# 02-Memory.net
KiCad netlist of a schematic drawn in Altium Designer
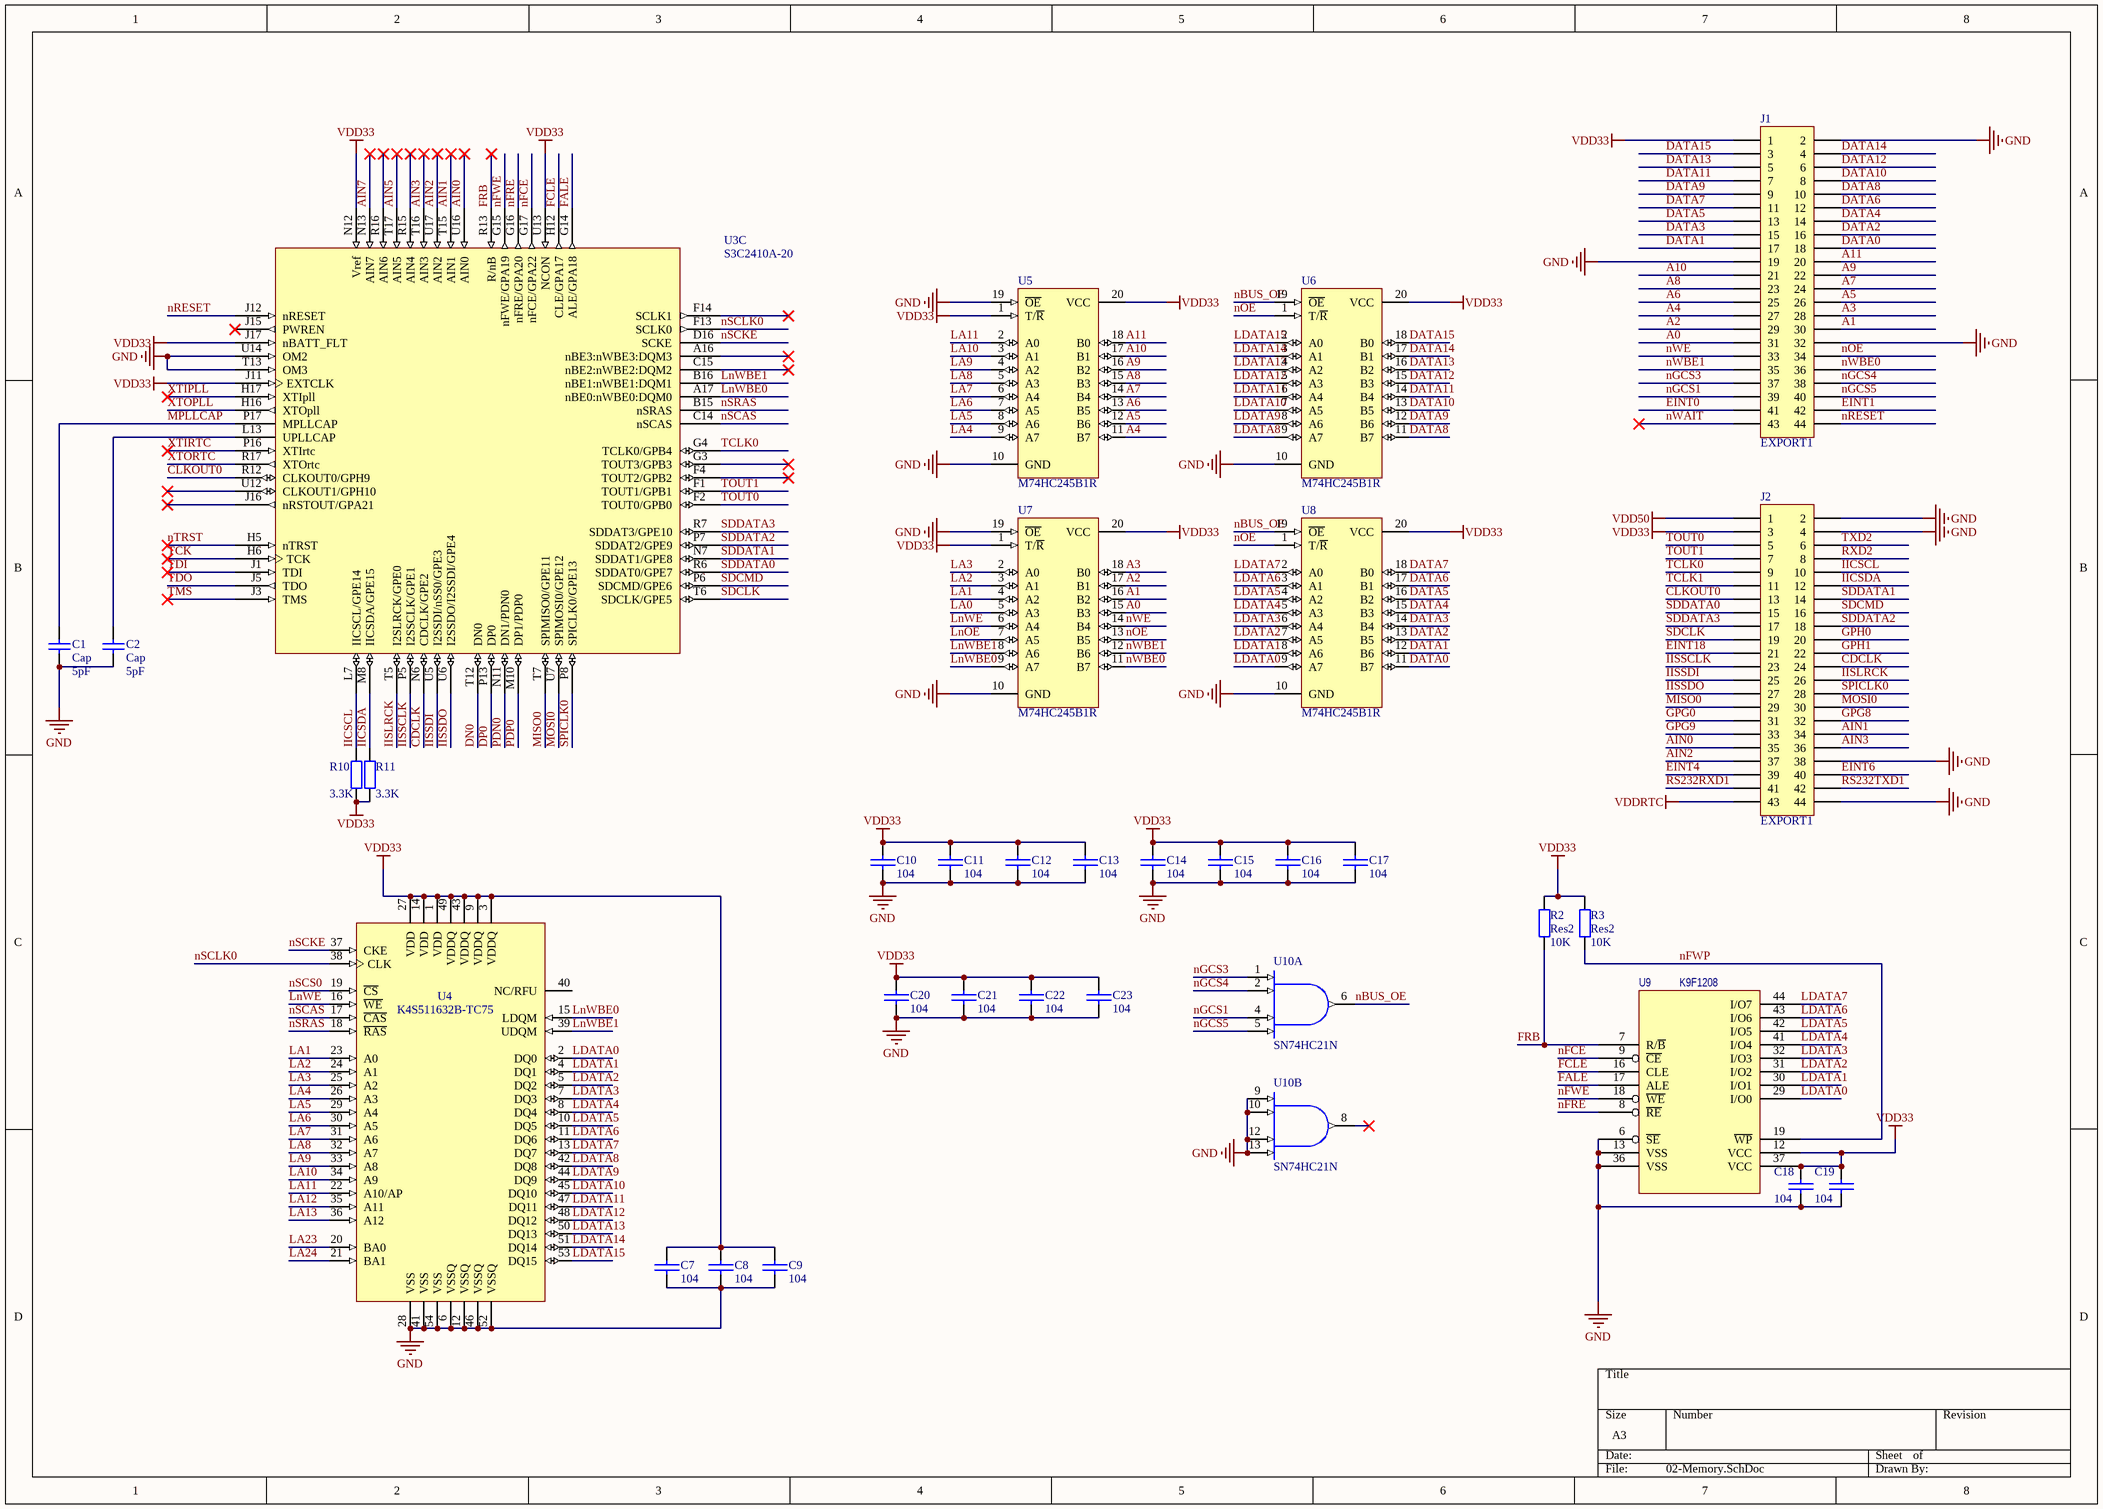
[diagram p0: 02-Memory.SchDoc]

(export (version "E")
  (design (tool "Eeschema 10.0.6"))
  (components
    (comp (ref "C1")
      (value "Cap")
      (footprint "RAD-0.3")
      (description "Capacitor")
      (fields (field (name "ALTIUM_VALUE") "5pF") (field (name "PUBLISHER") "Altium Limited"))
      (libsource (lib "Miscellaneous Devices") (part "Cap"))
    )
    (comp (ref "C2")
      (value "Cap")
      (footprint "RAD-0.3")
      (description "Capacitor")
      (fields (field (name "ALTIUM_VALUE") "5pF") (field (name "PUBLISHER") "Altium Limited"))
      (libsource (lib "Miscellaneous Devices") (part "Cap"))
    )
    (comp (ref "C7")
      (value "104")
      (footprint "A型钽电容")
      (description "Capacitor")
      (libsource (lib "ARM_DEMO") (part "CAP_1"))
    )
    (comp (ref "C8")
      (value "104")
      (footprint "A型钽电容")
      (description "Capacitor")
      (libsource (lib "ARM_DEMO") (part "CAP_1"))
    )
    (comp (ref "C9")
      (value "104")
      (footprint "A型钽电容")
      (description "Capacitor")
      (libsource (lib "ARM_DEMO") (part "CAP_1"))
    )
    (comp (ref "C10")
      (value "104")
      (footprint "A型钽电容")
      (description "Capacitor")
      (libsource (lib "ARM_DEMO") (part "CAP_1"))
    )
    (comp (ref "C11")
      (value "104")
      (footprint "A型钽电容")
      (description "Capacitor")
      (libsource (lib "ARM_DEMO") (part "CAP_1"))
    )
    (comp (ref "C12")
      (value "104")
      (footprint "A型钽电容")
      (description "Capacitor")
      (libsource (lib "ARM_DEMO") (part "CAP_1"))
    )
    (comp (ref "C13")
      (value "104")
      (footprint "A型钽电容")
      (description "Capacitor")
      (libsource (lib "ARM_DEMO") (part "CAP_1"))
    )
    (comp (ref "C14")
      (value "104")
      (footprint "A型钽电容")
      (description "Capacitor")
      (libsource (lib "ARM_DEMO") (part "CAP_1"))
    )
    (comp (ref "C15")
      (value "104")
      (footprint "A型钽电容")
      (description "Capacitor")
      (libsource (lib "ARM_DEMO") (part "CAP_1"))
    )
    (comp (ref "C16")
      (value "104")
      (footprint "A型钽电容")
      (description "Capacitor")
      (libsource (lib "ARM_DEMO") (part "CAP_1"))
    )
    (comp (ref "C17")
      (value "104")
      (footprint "A型钽电容")
      (description "Capacitor")
      (libsource (lib "ARM_DEMO") (part "CAP_1"))
    )
    (comp (ref "C18")
      (value "104")
      (footprint "A型钽电容")
      (description "Capacitor")
      (libsource (lib "ARM_DEMO") (part "CAP_1"))
    )
    (comp (ref "C19")
      (value "104")
      (footprint "A型钽电容")
      (description "Capacitor")
      (libsource (lib "ARM_DEMO") (part "CAP_1"))
    )
    (comp (ref "C20")
      (value "104")
      (footprint "A型钽电容")
      (description "Capacitor")
      (libsource (lib "ARM_DEMO") (part "CAP_1"))
    )
    (comp (ref "C21")
      (value "104")
      (footprint "A型钽电容")
      (description "Capacitor")
      (libsource (lib "ARM_DEMO") (part "CAP_1"))
    )
    (comp (ref "C22")
      (value "104")
      (footprint "A型钽电容")
      (description "Capacitor")
      (libsource (lib "ARM_DEMO") (part "CAP_1"))
    )
    (comp (ref "C23")
      (value "104")
      (footprint "A型钽电容")
      (description "Capacitor")
      (libsource (lib "ARM_DEMO") (part "CAP_1"))
    )
    (comp (ref "J1")
      (value "EXPORT1")
      (footprint "HDR2X22")
      (description "Header, 22-Pin, Dual row")
      (fields (field (name "PUBLISHER") "Altium Limited"))
      (libsource (lib "ARM_DEMO") (part "Header 22X2"))
    )
    (comp (ref "J2")
      (value "EXPORT1")
      (footprint "HDR2X22")
      (description "Header, 22-Pin, Dual row")
      (fields (field (name "PUBLISHER") "Altium Limited"))
      (libsource (lib "ARM_DEMO") (part "Header 22X2"))
    )
    (comp (ref "R2")
      (value "Res2")
      (footprint "0603R")
      (description "Resistor")
      (fields (field (name "ALTIUM_VALUE") "10K") (field (name "PUBLISHER") "Altium Limited"))
      (libsource (lib "ARM_DEMO") (part "Res2"))
    )
    (comp (ref "R3")
      (value "Res2")
      (footprint "0603R")
      (description "Resistor")
      (fields (field (name "ALTIUM_VALUE") "10K") (field (name "PUBLISHER") "Altium Limited"))
      (libsource (lib "ARM_DEMO") (part "Res2"))
    )
    (comp (ref "R10")
      (value "3.3K")
      (footprint "0603R")
      (description "Resistor")
      (fields (field (name "Comment") "Res2") (field (name "PUBLISHER") "Altium Limited"))
      (libsource (lib "ARM_DEMO") (part "Res2_1"))
    )
    (comp (ref "R11")
      (value "3.3K")
      (footprint "0603R")
      (description "Resistor")
      (fields (field (name "Comment") "Res2") (field (name "PUBLISHER") "Altium Limited"))
      (libsource (lib "ARM_DEMO") (part "Res2_1"))
    )
    (comp (ref "U3")
      (value "S3C2410A-20")
      (footprint "FBGA272")
      (description "32-Bit RISC Microprocessor, 200 MHz, 1.8V (Core), 3.3V (Memory and IO), 272-Pin FBGA")
      (fields (field (name "PUBLISHER") "Altium Limited"))
      (libsource (lib "ARM_DEMO") (part "S3C2410A-20"))
    )
    (comp (ref "U4")
      (value "K4S511632B-TC75")
      (footprint "54_TSOP2_400AF_N")
      (description "512Mb Synchronous High Data Rate DRAM, 8Mb x 16Bit x 4 Banks, 54-Pin TSOP")
      (fields (field (name "PUBLISHER") "Altium Limited"))
      (libsource (lib "ARM_DEMO") (part "K4S511632B-TC75"))
    )
    (comp (ref "U5")
      (value "M74HC245B1R")
      (footprint "SOP-20")
      (description "Octal Bus Transceiver 3-State Non-Inverting")
      (fields (field (name "PUBLISHER") "Altium Limited"))
      (libsource (lib "ARM_DEMO") (part "M74HC245B1R"))
    )
    (comp (ref "U6")
      (value "M74HC245B1R")
      (footprint "SOP-20")
      (description "Octal Bus Transceiver 3-State Non-Inverting")
      (fields (field (name "PUBLISHER") "Altium Limited"))
      (libsource (lib "ARM_DEMO") (part "M74HC245B1R"))
    )
    (comp (ref "U7")
      (value "M74HC245B1R")
      (footprint "SOP-20")
      (description "Octal Bus Transceiver 3-State Non-Inverting")
      (fields (field (name "PUBLISHER") "Altium Limited"))
      (libsource (lib "ARM_DEMO") (part "M74HC245B1R"))
    )
    (comp (ref "U8")
      (value "M74HC245B1R")
      (footprint "SOP-20")
      (description "Octal Bus Transceiver 3-State Non-Inverting")
      (fields (field (name "PUBLISHER") "Altium Limited"))
      (libsource (lib "ARM_DEMO") (part "M74HC245B1R"))
    )
    (comp (ref "U9") (value "K9F1208") (footprint "TSOP48") (libsource (lib "ARM_DEMO") (part "K9F2808")))
    (comp (ref "U10")
      (value "SN74HC21N")
      (footprint "N014")
      (description "Dual 4-Input Positive-AND Gate")
      (fields (field (name "PUBLISHER") "Altium Limited"))
      (libsource (lib "ARM_DEMO") (part "SN74HC21N"))
    )
  )
  (nets
    (net (code "1") (name "/A0") (class "Default")
      (node (ref "J1") (pin "31") (pinfunction "31_31") (pintype "passive"))
      (node (ref "U7") (pin "15") (pinfunction "B3_15") (pintype "bidirectional"))
    )
    (net (code "2") (name "/A1") (class "Default")
      (node (ref "J1") (pin "30") (pinfunction "30_30") (pintype "passive"))
      (node (ref "U7") (pin "16") (pinfunction "B2_16") (pintype "bidirectional"))
    )
    (net (code "3") (name "/A2") (class "Default")
      (node (ref "J1") (pin "29") (pinfunction "29_29") (pintype "passive"))
      (node (ref "U7") (pin "17") (pinfunction "B1_17") (pintype "bidirectional"))
    )
    (net (code "4") (name "/A3") (class "Default")
      (node (ref "J1") (pin "28") (pinfunction "28_28") (pintype "passive"))
      (node (ref "U7") (pin "18") (pinfunction "B0_18") (pintype "bidirectional"))
    )
    (net (code "5") (name "/A4") (class "Default")
      (node (ref "J1") (pin "27") (pinfunction "27_27") (pintype "passive"))
      (node (ref "U5") (pin "11") (pinfunction "B7_11") (pintype "bidirectional"))
    )
    (net (code "6") (name "/A5") (class "Default")
      (node (ref "J1") (pin "26") (pinfunction "26_26") (pintype "passive"))
      (node (ref "U5") (pin "12") (pinfunction "B6_12") (pintype "bidirectional"))
    )
    (net (code "7") (name "/A6") (class "Default")
      (node (ref "J1") (pin "25") (pinfunction "25_25") (pintype "passive"))
      (node (ref "U5") (pin "13") (pinfunction "B5_13") (pintype "bidirectional"))
    )
    (net (code "8") (name "/A7") (class "Default")
      (node (ref "J1") (pin "24") (pinfunction "24_24") (pintype "passive"))
      (node (ref "U5") (pin "14") (pinfunction "B4_14") (pintype "bidirectional"))
    )
    (net (code "9") (name "/A8") (class "Default")
      (node (ref "J1") (pin "23") (pinfunction "23_23") (pintype "passive"))
      (node (ref "U5") (pin "15") (pinfunction "B3_15") (pintype "bidirectional"))
    )
    (net (code "10") (name "/A9") (class "Default")
      (node (ref "J1") (pin "22") (pinfunction "22_22") (pintype "passive"))
      (node (ref "U5") (pin "16") (pinfunction "B2_16") (pintype "bidirectional"))
    )
    (net (code "11") (name "/A10") (class "Default")
      (node (ref "J1") (pin "21") (pinfunction "21_21") (pintype "passive"))
      (node (ref "U5") (pin "17") (pinfunction "B1_17") (pintype "bidirectional"))
    )
    (net (code "12") (name "/A11") (class "Default")
      (node (ref "J1") (pin "20") (pinfunction "20_20") (pintype "passive"))
      (node (ref "U5") (pin "18") (pinfunction "B0_18") (pintype "bidirectional"))
    )
    (net (code "13") (name "/AIN0") (class "Default")
      (node (ref "J2") (pin "35") (pinfunction "35_35") (pintype "passive"))
      (node (ref "U3") (pin "U16") (pinfunction "AIN0_U16") (pintype "input"))
    )
    (net (code "14") (name "/AIN1") (class "Default")
      (node (ref "J2") (pin "34") (pinfunction "34_34") (pintype "passive"))
      (node (ref "U3") (pin "T15") (pinfunction "AIN1_T15") (pintype "input"))
    )
    (net (code "15") (name "/AIN2") (class "Default")
      (node (ref "J2") (pin "37") (pinfunction "37_37") (pintype "passive"))
      (node (ref "U3") (pin "U17") (pinfunction "AIN2_U17") (pintype "input"))
    )
    (net (code "16") (name "/AIN3") (class "Default")
      (node (ref "J2") (pin "36") (pinfunction "36_36") (pintype "passive"))
      (node (ref "U3") (pin "T16") (pinfunction "AIN3_T16") (pintype "input"))
    )
    (net (code "17") (name "/AIN5") (class "Default")
      (node (ref "U3") (pin "T17") (pinfunction "AIN5_T17") (pintype "input+no_connect"))
    )
    (net (code "18") (name "/AIN7") (class "Default")
      (node (ref "U3") (pin "N13") (pinfunction "AIN7_N13") (pintype "input+no_connect"))
    )
    (net (code "19") (name "/CDCLK") (class "Default")
      (node (ref "J2") (pin "24") (pinfunction "24_24") (pintype "passive"))
      (node (ref "U3") (pin "N6") (pinfunction "CDCLK/GPE2_N6") (pintype "bidirectional"))
    )
    (net (code "20") (name "/CLKOUT0") (class "Default")
      (node (ref "J2") (pin "13") (pinfunction "13_13") (pintype "passive"))
      (node (ref "U3") (pin "R12") (pinfunction "CLKOUT0/GPH9_R12") (pintype "bidirectional"))
    )
    (net (code "21") (name "/DATA0") (class "Default")
      (node (ref "J1") (pin "18") (pinfunction "18_18") (pintype "passive"))
      (node (ref "U8") (pin "11") (pinfunction "B7_11") (pintype "bidirectional"))
    )
    (net (code "22") (name "/DATA1") (class "Default")
      (node (ref "J1") (pin "17") (pinfunction "17_17") (pintype "passive"))
      (node (ref "U8") (pin "12") (pinfunction "B6_12") (pintype "bidirectional"))
    )
    (net (code "23") (name "/DATA2") (class "Default")
      (node (ref "J1") (pin "16") (pinfunction "16_16") (pintype "passive"))
      (node (ref "U8") (pin "13") (pinfunction "B5_13") (pintype "bidirectional"))
    )
    (net (code "24") (name "/DATA3") (class "Default")
      (node (ref "J1") (pin "15") (pinfunction "15_15") (pintype "passive"))
      (node (ref "U8") (pin "14") (pinfunction "B4_14") (pintype "bidirectional"))
    )
    (net (code "25") (name "/DATA4") (class "Default")
      (node (ref "J1") (pin "14") (pinfunction "14_14") (pintype "passive"))
      (node (ref "U8") (pin "15") (pinfunction "B3_15") (pintype "bidirectional"))
    )
    (net (code "26") (name "/DATA5") (class "Default")
      (node (ref "J1") (pin "13") (pinfunction "13_13") (pintype "passive"))
      (node (ref "U8") (pin "16") (pinfunction "B2_16") (pintype "bidirectional"))
    )
    (net (code "27") (name "/DATA6") (class "Default")
      (node (ref "J1") (pin "12") (pinfunction "12_12") (pintype "passive"))
      (node (ref "U8") (pin "17") (pinfunction "B1_17") (pintype "bidirectional"))
    )
    (net (code "28") (name "/DATA7") (class "Default")
      (node (ref "J1") (pin "11") (pinfunction "11_11") (pintype "passive"))
      (node (ref "U8") (pin "18") (pinfunction "B0_18") (pintype "bidirectional"))
    )
    (net (code "29") (name "/DATA8") (class "Default")
      (node (ref "J1") (pin "10") (pinfunction "10_10") (pintype "passive"))
      (node (ref "U6") (pin "11") (pinfunction "B7_11") (pintype "bidirectional"))
    )
    (net (code "30") (name "/DATA9") (class "Default")
      (node (ref "J1") (pin "9") (pinfunction "9_9") (pintype "passive"))
      (node (ref "U6") (pin "12") (pinfunction "B6_12") (pintype "bidirectional"))
    )
    (net (code "31") (name "/DATA10") (class "Default")
      (node (ref "J1") (pin "8") (pinfunction "8_8") (pintype "passive"))
      (node (ref "U6") (pin "13") (pinfunction "B5_13") (pintype "bidirectional"))
    )
    (net (code "32") (name "/DATA11") (class "Default")
      (node (ref "J1") (pin "7") (pinfunction "7_7") (pintype "passive"))
      (node (ref "U6") (pin "14") (pinfunction "B4_14") (pintype "bidirectional"))
    )
    (net (code "33") (name "/DATA12") (class "Default")
      (node (ref "J1") (pin "6") (pinfunction "6_6") (pintype "passive"))
      (node (ref "U6") (pin "15") (pinfunction "B3_15") (pintype "bidirectional"))
    )
    (net (code "34") (name "/DATA13") (class "Default")
      (node (ref "J1") (pin "5") (pinfunction "5_5") (pintype "passive"))
      (node (ref "U6") (pin "16") (pinfunction "B2_16") (pintype "bidirectional"))
    )
    (net (code "35") (name "/DATA14") (class "Default")
      (node (ref "J1") (pin "4") (pinfunction "4_4") (pintype "passive"))
      (node (ref "U6") (pin "17") (pinfunction "B1_17") (pintype "bidirectional"))
    )
    (net (code "36") (name "/DATA15") (class "Default")
      (node (ref "J1") (pin "3") (pinfunction "3_3") (pintype "passive"))
      (node (ref "U6") (pin "18") (pinfunction "B0_18") (pintype "bidirectional"))
    )
    (net (code "37") (name "/DN0") (class "Default")
      (node (ref "U3") (pin "T12") (pinfunction "DN0_T12") (pintype "bidirectional"))
    )
    (net (code "38") (name "/DP0") (class "Default")
      (node (ref "U3") (pin "P13") (pinfunction "DP0_P13") (pintype "bidirectional"))
    )
    (net (code "39") (name "/EINT0") (class "Default")
      (node (ref "J1") (pin "41") (pinfunction "41_41") (pintype "passive"))
    )
    (net (code "40") (name "/EINT1") (class "Default")
      (node (ref "J1") (pin "42") (pinfunction "42_42") (pintype "passive"))
    )
    (net (code "41") (name "/EINT4") (class "Default")
      (node (ref "J2") (pin "39") (pinfunction "39_39") (pintype "passive"))
    )
    (net (code "42") (name "/EINT6") (class "Default")
      (node (ref "J2") (pin "40") (pinfunction "40_40") (pintype "passive"))
    )
    (net (code "43") (name "/EINT18") (class "Default")
      (node (ref "J2") (pin "21") (pinfunction "21_21") (pintype "passive"))
    )
    (net (code "44") (name "/FALE") (class "Default")
      (node (ref "U3") (pin "G14") (pinfunction "ALE/GPA18_G14") (pintype "output"))
      (node (ref "U9") (pin "17") (pinfunction "ALE_17") (pintype "passive"))
    )
    (net (code "45") (name "/FCLE") (class "Default")
      (node (ref "U3") (pin "H12") (pinfunction "CLE/GPA17_H12") (pintype "output"))
      (node (ref "U9") (pin "16") (pinfunction "CLE_16") (pintype "passive"))
    )
    (net (code "46") (name "/FRB") (class "Default")
      (node (ref "R2") (pin "1") (pinfunction "1_1") (pintype "passive"))
      (node (ref "U3") (pin "R13") (pinfunction "R/nB_R13") (pintype "input"))
      (node (ref "U9") (pin "7") (pinfunction "R/~{B}_7") (pintype "passive"))
    )
    (net (code "47") (name "/GPG0") (class "Default")
      (node (ref "J2") (pin "31") (pinfunction "31_31") (pintype "passive"))
    )
    (net (code "48") (name "/GPG8") (class "Default")
      (node (ref "J2") (pin "32") (pinfunction "32_32") (pintype "passive"))
    )
    (net (code "49") (name "/GPG9") (class "Default")
      (node (ref "J2") (pin "33") (pinfunction "33_33") (pintype "passive"))
    )
    (net (code "50") (name "/GPH0") (class "Default")
      (node (ref "J2") (pin "20") (pinfunction "20_20") (pintype "passive"))
    )
    (net (code "51") (name "/GPH1") (class "Default")
      (node (ref "J2") (pin "22") (pinfunction "22_22") (pintype "passive"))
    )
    (net (code "52") (name "/IICSCL") (class "Default")
      (node (ref "J2") (pin "10") (pinfunction "10_10") (pintype "passive"))
      (node (ref "R10") (pin "2") (pinfunction "2_2") (pintype "passive"))
      (node (ref "U3") (pin "L7") (pinfunction "IICSCL/GPE14_L7") (pintype "bidirectional"))
    )
    (net (code "53") (name "/IICSDA") (class "Default")
      (node (ref "J2") (pin "12") (pinfunction "12_12") (pintype "passive"))
      (node (ref "R11") (pin "2") (pinfunction "2_2") (pintype "passive"))
      (node (ref "U3") (pin "M8") (pinfunction "IICSDA/GPE15_M8") (pintype "bidirectional"))
    )
    (net (code "54") (name "/IISLRCK") (class "Default")
      (node (ref "J2") (pin "26") (pinfunction "26_26") (pintype "passive"))
      (node (ref "U3") (pin "T5") (pinfunction "I2SLRCK/GPE0_T5") (pintype "bidirectional"))
    )
    (net (code "55") (name "/IISSCLK") (class "Default")
      (node (ref "J2") (pin "23") (pinfunction "23_23") (pintype "passive"))
      (node (ref "U3") (pin "P5") (pinfunction "I2SSCLK/GPE1_P5") (pintype "bidirectional"))
    )
    (net (code "56") (name "/IISSDI") (class "Default")
      (node (ref "J2") (pin "25") (pinfunction "25_25") (pintype "passive"))
      (node (ref "U3") (pin "U5") (pinfunction "I2SSDI/nSS0/GPE3_U5") (pintype "bidirectional"))
    )
    (net (code "57") (name "/IISSDO") (class "Default")
      (node (ref "J2") (pin "27") (pinfunction "27_27") (pintype "passive"))
      (node (ref "U3") (pin "U6") (pinfunction "I2SSDO/I2SSDI/GPE4_U6") (pintype "bidirectional"))
    )
    (net (code "58") (name "/LA0") (class "Default")
      (node (ref "U7") (pin "5") (pinfunction "A3_5") (pintype "bidirectional"))
    )
    (net (code "59") (name "/LA1") (class "Default")
      (node (ref "U4") (pin "23") (pinfunction "A0_23") (pintype "input"))
      (node (ref "U7") (pin "4") (pinfunction "A2_4") (pintype "bidirectional"))
    )
    (net (code "60") (name "/LA2") (class "Default")
      (node (ref "U4") (pin "24") (pinfunction "A1_24") (pintype "input"))
      (node (ref "U7") (pin "3") (pinfunction "A1_3") (pintype "bidirectional"))
    )
    (net (code "61") (name "/LA3") (class "Default")
      (node (ref "U4") (pin "25") (pinfunction "A2_25") (pintype "input"))
      (node (ref "U7") (pin "2") (pinfunction "A0_2") (pintype "bidirectional"))
    )
    (net (code "62") (name "/LA4") (class "Default")
      (node (ref "U4") (pin "26") (pinfunction "A3_26") (pintype "input"))
      (node (ref "U5") (pin "9") (pinfunction "A7_9") (pintype "bidirectional"))
    )
    (net (code "63") (name "/LA5") (class "Default")
      (node (ref "U4") (pin "29") (pinfunction "A4_29") (pintype "input"))
      (node (ref "U5") (pin "8") (pinfunction "A6_8") (pintype "bidirectional"))
    )
    (net (code "64") (name "/LA6") (class "Default")
      (node (ref "U4") (pin "30") (pinfunction "A5_30") (pintype "input"))
      (node (ref "U5") (pin "7") (pinfunction "A5_7") (pintype "bidirectional"))
    )
    (net (code "65") (name "/LA7") (class "Default")
      (node (ref "U4") (pin "31") (pinfunction "A6_31") (pintype "input"))
      (node (ref "U5") (pin "6") (pinfunction "A4_6") (pintype "bidirectional"))
    )
    (net (code "66") (name "/LA8") (class "Default")
      (node (ref "U4") (pin "32") (pinfunction "A7_32") (pintype "input"))
      (node (ref "U5") (pin "5") (pinfunction "A3_5") (pintype "bidirectional"))
    )
    (net (code "67") (name "/LA9") (class "Default")
      (node (ref "U4") (pin "33") (pinfunction "A8_33") (pintype "input"))
      (node (ref "U5") (pin "4") (pinfunction "A2_4") (pintype "bidirectional"))
    )
    (net (code "68") (name "/LA10") (class "Default")
      (node (ref "U4") (pin "34") (pinfunction "A9_34") (pintype "input"))
      (node (ref "U5") (pin "3") (pinfunction "A1_3") (pintype "bidirectional"))
    )
    (net (code "69") (name "/LA11") (class "Default")
      (node (ref "U4") (pin "22") (pinfunction "A10/AP_22") (pintype "input"))
      (node (ref "U5") (pin "2") (pinfunction "A0_2") (pintype "bidirectional"))
    )
    (net (code "70") (name "/LA12") (class "Default")
      (node (ref "U4") (pin "35") (pinfunction "A11_35") (pintype "input"))
    )
    (net (code "71") (name "/LA13") (class "Default")
      (node (ref "U4") (pin "36") (pinfunction "A12_36") (pintype "input"))
    )
    (net (code "72") (name "/LA23") (class "Default")
      (node (ref "U4") (pin "20") (pinfunction "BA0_20") (pintype "input"))
    )
    (net (code "73") (name "/LA24") (class "Default")
      (node (ref "U4") (pin "21") (pinfunction "BA1_21") (pintype "input"))
    )
    (net (code "74") (name "/LDATA0") (class "Default")
      (node (ref "U4") (pin "2") (pinfunction "DQ0_2") (pintype "bidirectional"))
      (node (ref "U8") (pin "9") (pinfunction "A7_9") (pintype "bidirectional"))
      (node (ref "U9") (pin "29") (pinfunction "I/O0_29") (pintype "passive"))
    )
    (net (code "75") (name "/LDATA1") (class "Default")
      (node (ref "U4") (pin "4") (pinfunction "DQ1_4") (pintype "bidirectional"))
      (node (ref "U8") (pin "8") (pinfunction "A6_8") (pintype "bidirectional"))
      (node (ref "U9") (pin "30") (pinfunction "I/O1_30") (pintype "passive"))
    )
    (net (code "76") (name "/LDATA2") (class "Default")
      (node (ref "U4") (pin "5") (pinfunction "DQ2_5") (pintype "bidirectional"))
      (node (ref "U8") (pin "7") (pinfunction "A5_7") (pintype "bidirectional"))
      (node (ref "U9") (pin "31") (pinfunction "I/O2_31") (pintype "passive"))
    )
    (net (code "77") (name "/LDATA3") (class "Default")
      (node (ref "U4") (pin "7") (pinfunction "DQ3_7") (pintype "bidirectional"))
      (node (ref "U8") (pin "6") (pinfunction "A4_6") (pintype "bidirectional"))
      (node (ref "U9") (pin "32") (pinfunction "I/O3_32") (pintype "passive"))
    )
    (net (code "78") (name "/LDATA4") (class "Default")
      (node (ref "U4") (pin "8") (pinfunction "DQ4_8") (pintype "bidirectional"))
      (node (ref "U8") (pin "5") (pinfunction "A3_5") (pintype "bidirectional"))
      (node (ref "U9") (pin "41") (pinfunction "I/O4_41") (pintype "passive"))
    )
    (net (code "79") (name "/LDATA5") (class "Default")
      (node (ref "U4") (pin "10") (pinfunction "DQ5_10") (pintype "bidirectional"))
      (node (ref "U8") (pin "4") (pinfunction "A2_4") (pintype "bidirectional"))
      (node (ref "U9") (pin "42") (pinfunction "I/O5_42") (pintype "passive"))
    )
    (net (code "80") (name "/LDATA6") (class "Default")
      (node (ref "U4") (pin "11") (pinfunction "DQ6_11") (pintype "bidirectional"))
      (node (ref "U8") (pin "3") (pinfunction "A1_3") (pintype "bidirectional"))
      (node (ref "U9") (pin "43") (pinfunction "I/O6_43") (pintype "passive"))
    )
    (net (code "81") (name "/LDATA7") (class "Default")
      (node (ref "U4") (pin "13") (pinfunction "DQ7_13") (pintype "bidirectional"))
      (node (ref "U8") (pin "2") (pinfunction "A0_2") (pintype "bidirectional"))
      (node (ref "U9") (pin "44") (pinfunction "I/O7_44") (pintype "passive"))
    )
    (net (code "82") (name "/LDATA8") (class "Default")
      (node (ref "U4") (pin "42") (pinfunction "DQ8_42") (pintype "bidirectional"))
      (node (ref "U6") (pin "9") (pinfunction "A7_9") (pintype "bidirectional"))
    )
    (net (code "83") (name "/LDATA9") (class "Default")
      (node (ref "U4") (pin "44") (pinfunction "DQ9_44") (pintype "bidirectional"))
      (node (ref "U6") (pin "8") (pinfunction "A6_8") (pintype "bidirectional"))
    )
    (net (code "84") (name "/LDATA10") (class "Default")
      (node (ref "U4") (pin "45") (pinfunction "DQ10_45") (pintype "bidirectional"))
      (node (ref "U6") (pin "7") (pinfunction "A5_7") (pintype "bidirectional"))
    )
    (net (code "85") (name "/LDATA11") (class "Default")
      (node (ref "U4") (pin "47") (pinfunction "DQ11_47") (pintype "bidirectional"))
      (node (ref "U6") (pin "6") (pinfunction "A4_6") (pintype "bidirectional"))
    )
    (net (code "86") (name "/LDATA12") (class "Default")
      (node (ref "U4") (pin "48") (pinfunction "DQ12_48") (pintype "bidirectional"))
      (node (ref "U6") (pin "5") (pinfunction "A3_5") (pintype "bidirectional"))
    )
    (net (code "87") (name "/LDATA13") (class "Default")
      (node (ref "U4") (pin "50") (pinfunction "DQ13_50") (pintype "bidirectional"))
      (node (ref "U6") (pin "4") (pinfunction "A2_4") (pintype "bidirectional"))
    )
    (net (code "88") (name "/LDATA14") (class "Default")
      (node (ref "U4") (pin "51") (pinfunction "DQ14_51") (pintype "bidirectional"))
      (node (ref "U6") (pin "3") (pinfunction "A1_3") (pintype "bidirectional"))
    )
    (net (code "89") (name "/LDATA15") (class "Default")
      (node (ref "U4") (pin "53") (pinfunction "DQ15_53") (pintype "bidirectional"))
      (node (ref "U6") (pin "2") (pinfunction "A0_2") (pintype "bidirectional"))
    )
    (net (code "90") (name "/LnOE") (class "Default")
      (node (ref "U7") (pin "7") (pinfunction "A5_7") (pintype "bidirectional"))
    )
    (net (code "91") (name "/LnWBE0") (class "Default")
      (node (ref "U3") (pin "A17") (pinfunction "nBE0:nWBE0:DQM0_A17") (pintype "tri_state"))
      (node (ref "U4") (pin "15") (pinfunction "LDQM_15") (pintype "input"))
      (node (ref "U7") (pin "9") (pinfunction "A7_9") (pintype "bidirectional"))
    )
    (net (code "92") (name "/LnWBE1") (class "Default")
      (node (ref "U3") (pin "B16") (pinfunction "nBE1:nWBE1:DQM1_B16") (pintype "tri_state"))
      (node (ref "U4") (pin "39") (pinfunction "UDQM_39") (pintype "input"))
      (node (ref "U7") (pin "8") (pinfunction "A6_8") (pintype "bidirectional"))
    )
    (net (code "93") (name "/LnWE") (class "Default")
      (node (ref "U4") (pin "16") (pinfunction "~{WE}_16") (pintype "input"))
      (node (ref "U7") (pin "6") (pinfunction "A4_6") (pintype "bidirectional"))
    )
    (net (code "94") (name "/MISO0") (class "Default")
      (node (ref "J2") (pin "29") (pinfunction "29_29") (pintype "passive"))
      (node (ref "U3") (pin "T7") (pinfunction "SPIMISO0/GPE11_T7") (pintype "bidirectional"))
    )
    (net (code "95") (name "/MOSI0") (class "Default")
      (node (ref "J2") (pin "30") (pinfunction "30_30") (pintype "passive"))
      (node (ref "U3") (pin "U7") (pinfunction "SPIMOSI0/GPE12_U7") (pintype "bidirectional"))
    )
    (net (code "96") (name "/MPLLCAP") (class "Default")
      (node (ref "C1") (pin "2") (pinfunction "2_2") (pintype "passive"))
      (node (ref "U3") (pin "P17") (pinfunction "MPLLCAP_P17") (pintype "passive"))
    )
    (net (code "97") (name "/PDN0") (class "Default")
      (node (ref "U3") (pin "N11") (pinfunction "DN1/PDN0_N11") (pintype "bidirectional"))
    )
    (net (code "98") (name "/PDP0") (class "Default")
      (node (ref "U3") (pin "M10") (pinfunction "DP1/PDP0_M10") (pintype "bidirectional"))
    )
    (net (code "99") (name "/RS232RXD1") (class "Default")
      (node (ref "J2") (pin "41") (pinfunction "41_41") (pintype "passive"))
    )
    (net (code "100") (name "/RS232TXD1") (class "Default")
      (node (ref "J2") (pin "42") (pinfunction "42_42") (pintype "passive"))
    )
    (net (code "101") (name "/RXD2") (class "Default")
      (node (ref "J2") (pin "8") (pinfunction "8_8") (pintype "passive"))
    )
    (net (code "102") (name "/SDCLK") (class "Default")
      (node (ref "J2") (pin "19") (pinfunction "19_19") (pintype "passive"))
      (node (ref "U3") (pin "T6") (pinfunction "SDCLK/GPE5_T6") (pintype "bidirectional"))
    )
    (net (code "103") (name "/SDCMD") (class "Default")
      (node (ref "J2") (pin "16") (pinfunction "16_16") (pintype "passive"))
      (node (ref "U3") (pin "P6") (pinfunction "SDCMD/GPE6_P6") (pintype "bidirectional"))
    )
    (net (code "104") (name "/SDDATA0") (class "Default")
      (node (ref "J2") (pin "15") (pinfunction "15_15") (pintype "passive"))
      (node (ref "U3") (pin "R6") (pinfunction "SDDAT0/GPE7_R6") (pintype "bidirectional"))
    )
    (net (code "105") (name "/SDDATA1") (class "Default")
      (node (ref "J2") (pin "14") (pinfunction "14_14") (pintype "passive"))
      (node (ref "U3") (pin "N7") (pinfunction "SDDAT1/GPE8_N7") (pintype "bidirectional"))
    )
    (net (code "106") (name "/SDDATA2") (class "Default")
      (node (ref "J2") (pin "18") (pinfunction "18_18") (pintype "passive"))
      (node (ref "U3") (pin "P7") (pinfunction "SDDAT2/GPE9_P7") (pintype "bidirectional"))
    )
    (net (code "107") (name "/SDDATA3") (class "Default")
      (node (ref "J2") (pin "17") (pinfunction "17_17") (pintype "passive"))
      (node (ref "U3") (pin "R7") (pinfunction "SDDAT3/GPE10_R7") (pintype "bidirectional"))
    )
    (net (code "108") (name "/SPICLK0") (class "Default")
      (node (ref "J2") (pin "28") (pinfunction "28_28") (pintype "passive"))
      (node (ref "U3") (pin "P8") (pinfunction "SPICLK0/GPE13_P8") (pintype "bidirectional"))
    )
    (net (code "109") (name "/TCK") (class "Default")
      (node (ref "U3") (pin "H6") (pinfunction "TCK_H6") (pintype "input+no_connect"))
    )
    (net (code "110") (name "/TCLK0") (class "Default")
      (node (ref "J2") (pin "9") (pinfunction "9_9") (pintype "passive"))
      (node (ref "U3") (pin "G4") (pinfunction "TCLK0/GPB4_G4") (pintype "bidirectional"))
    )
    (net (code "111") (name "/TCLK1") (class "Default")
      (node (ref "J2") (pin "11") (pinfunction "11_11") (pintype "passive"))
    )
    (net (code "112") (name "/TDI") (class "Default")
      (node (ref "U3") (pin "J1") (pinfunction "TDI_J1") (pintype "input+no_connect"))
    )
    (net (code "113") (name "/TDO") (class "Default")
      (node (ref "U3") (pin "J5") (pinfunction "TDO_J5") (pintype "output"))
    )
    (net (code "114") (name "/TMS") (class "Default")
      (node (ref "U3") (pin "J3") (pinfunction "TMS_J3") (pintype "input+no_connect"))
    )
    (net (code "115") (name "/TOUT0") (class "Default")
      (node (ref "J2") (pin "5") (pinfunction "5_5") (pintype "passive"))
      (node (ref "U3") (pin "F2") (pinfunction "TOUT0/GPB0_F2") (pintype "bidirectional"))
    )
    (net (code "116") (name "/TOUT1") (class "Default")
      (node (ref "J2") (pin "7") (pinfunction "7_7") (pintype "passive"))
      (node (ref "U3") (pin "F1") (pinfunction "TOUT1/GPB1_F1") (pintype "bidirectional"))
    )
    (net (code "117") (name "/TXD2") (class "Default")
      (node (ref "J2") (pin "6") (pinfunction "6_6") (pintype "passive"))
    )
    (net (code "118") (name "/XTIPLL") (class "Default")
      (node (ref "U3") (pin "H17") (pinfunction "XTIpll_H17") (pintype "input+no_connect"))
    )
    (net (code "119") (name "/XTIRTC") (class "Default")
      (node (ref "U3") (pin "P16") (pinfunction "XTIrtc_P16") (pintype "input+no_connect"))
    )
    (net (code "120") (name "/XTOPLL") (class "Default")
      (node (ref "U3") (pin "H16") (pinfunction "XTOpll_H16") (pintype "output"))
    )
    (net (code "121") (name "/XTORTC") (class "Default")
      (node (ref "U3") (pin "R17") (pinfunction "XTOrtc_R17") (pintype "output"))
    )
    (net (code "122") (name "/nBUS_OE") (class "Default")
      (node (ref "U10") (pin "6") (pinfunction "Y_6") (pintype "output"))
      (node (ref "U6") (pin "19") (pinfunction "~{OE}_19") (pintype "input"))
      (node (ref "U8") (pin "19") (pinfunction "~{OE}_19") (pintype "input"))
    )
    (net (code "123") (name "/nFCE") (class "Default")
      (node (ref "U3") (pin "G17") (pinfunction "nFCE/GPA22_G17") (pintype "output"))
      (node (ref "U9") (pin "9") (pinfunction "~{CE}_9") (pintype "passive"))
    )
    (net (code "124") (name "/nFRE") (class "Default")
      (node (ref "U3") (pin "G16") (pinfunction "nFRE/GPA20_G16") (pintype "output"))
      (node (ref "U9") (pin "8") (pinfunction "~{RE}_8") (pintype "passive"))
    )
    (net (code "125") (name "/nFWE") (class "Default")
      (node (ref "U3") (pin "G15") (pinfunction "nFWE/GPA19_G15") (pintype "output"))
      (node (ref "U9") (pin "18") (pinfunction "~{WE}_18") (pintype "passive"))
    )
    (net (code "126") (name "/nFWP") (class "Default")
      (node (ref "R3") (pin "1") (pinfunction "1_1") (pintype "passive"))
      (node (ref "U9") (pin "19") (pinfunction "~{WP}_19") (pintype "passive"))
    )
    (net (code "127") (name "/nGCS1") (class "Default")
      (node (ref "J1") (pin "39") (pinfunction "39_39") (pintype "passive"))
      (node (ref "U10") (pin "4") (pinfunction "C_4") (pintype "input"))
    )
    (net (code "128") (name "/nGCS3") (class "Default")
      (node (ref "J1") (pin "37") (pinfunction "37_37") (pintype "passive"))
      (node (ref "U10") (pin "1") (pinfunction "A_1") (pintype "input"))
    )
    (net (code "129") (name "/nGCS4") (class "Default")
      (node (ref "J1") (pin "38") (pinfunction "38_38") (pintype "passive"))
      (node (ref "U10") (pin "2") (pinfunction "B_2") (pintype "input"))
    )
    (net (code "130") (name "/nGCS5") (class "Default")
      (node (ref "J1") (pin "40") (pinfunction "40_40") (pintype "passive"))
      (node (ref "U10") (pin "5") (pinfunction "D_5") (pintype "input"))
    )
    (net (code "131") (name "/nOE") (class "Default")
      (node (ref "J1") (pin "34") (pinfunction "34_34") (pintype "passive"))
      (node (ref "U6") (pin "1") (pinfunction "T/~{R}_1") (pintype "input"))
      (node (ref "U7") (pin "13") (pinfunction "B5_13") (pintype "bidirectional"))
      (node (ref "U8") (pin "1") (pinfunction "T/~{R}_1") (pintype "input"))
    )
    (net (code "132") (name "/nRESET") (class "Default")
      (node (ref "J1") (pin "44") (pinfunction "44_44") (pintype "passive"))
      (node (ref "U3") (pin "J12") (pinfunction "nRESET_J12") (pintype "input"))
    )
    (net (code "133") (name "/nSCAS") (class "Default")
      (node (ref "U3") (pin "C14") (pinfunction "nSCAS_C14") (pintype "tri_state"))
      (node (ref "U4") (pin "17") (pinfunction "~{CAS}_17") (pintype "input"))
    )
    (net (code "134") (name "/nSCKE") (class "Default")
      (node (ref "U3") (pin "D16") (pinfunction "SCKE_D16") (pintype "tri_state"))
      (node (ref "U4") (pin "37") (pinfunction "CKE_37") (pintype "input"))
    )
    (net (code "135") (name "/nSCLK0") (class "Default")
      (node (ref "U3") (pin "F13") (pinfunction "SCLK0_F13") (pintype "output"))
      (node (ref "U4") (pin "38") (pinfunction "CLK_38") (pintype "input"))
    )
    (net (code "136") (name "/nSCS0") (class "Default")
      (node (ref "U4") (pin "19") (pinfunction "~{CS}_19") (pintype "input"))
    )
    (net (code "137") (name "/nSRAS") (class "Default")
      (node (ref "U3") (pin "B15") (pinfunction "nSRAS_B15") (pintype "tri_state"))
      (node (ref "U4") (pin "18") (pinfunction "~{RAS}_18") (pintype "input"))
    )
    (net (code "138") (name "/nTRST") (class "Default")
      (node (ref "U3") (pin "H5") (pinfunction "nTRST_H5") (pintype "input+no_connect"))
    )
    (net (code "139") (name "/nWAIT") (class "Default")
      (node (ref "J1") (pin "43") (pinfunction "43_43") (pintype "passive+no_connect"))
    )
    (net (code "140") (name "/nWBE0") (class "Default")
      (node (ref "J1") (pin "36") (pinfunction "36_36") (pintype "passive"))
      (node (ref "U7") (pin "11") (pinfunction "B7_11") (pintype "bidirectional"))
    )
    (net (code "141") (name "/nWBE1") (class "Default")
      (node (ref "J1") (pin "35") (pinfunction "35_35") (pintype "passive"))
      (node (ref "U7") (pin "12") (pinfunction "B6_12") (pintype "bidirectional"))
    )
    (net (code "142") (name "/nWE") (class "Default")
      (node (ref "J1") (pin "33") (pinfunction "33_33") (pintype "passive"))
      (node (ref "U7") (pin "14") (pinfunction "B4_14") (pintype "bidirectional"))
    )
    (net (code "143") (name "GND") (class "Default")
      (node (ref "C1") (pin "1") (pinfunction "1_1") (pintype "passive"))
      (node (ref "C10") (pin "2") (pinfunction "2_2") (pintype "passive"))
      (node (ref "C11") (pin "2") (pinfunction "2_2") (pintype "passive"))
      (node (ref "C12") (pin "2") (pinfunction "2_2") (pintype "passive"))
      (node (ref "C13") (pin "2") (pinfunction "2_2") (pintype "passive"))
      (node (ref "C14") (pin "2") (pinfunction "2_2") (pintype "passive"))
      (node (ref "C15") (pin "2") (pinfunction "2_2") (pintype "passive"))
      (node (ref "C16") (pin "2") (pinfunction "2_2") (pintype "passive"))
      (node (ref "C17") (pin "2") (pinfunction "2_2") (pintype "passive"))
      (node (ref "C18") (pin "2") (pinfunction "2_2") (pintype "passive"))
      (node (ref "C19") (pin "2") (pinfunction "2_2") (pintype "passive"))
      (node (ref "C2") (pin "1") (pinfunction "1_1") (pintype "passive"))
      (node (ref "C20") (pin "2") (pinfunction "2_2") (pintype "passive"))
      (node (ref "C21") (pin "2") (pinfunction "2_2") (pintype "passive"))
      (node (ref "C22") (pin "2") (pinfunction "2_2") (pintype "passive"))
      (node (ref "C23") (pin "2") (pinfunction "2_2") (pintype "passive"))
      (node (ref "C7") (pin "2") (pinfunction "2_2") (pintype "passive"))
      (node (ref "C8") (pin "2") (pinfunction "2_2") (pintype "passive"))
      (node (ref "C9") (pin "2") (pinfunction "2_2") (pintype "passive"))
      (node (ref "J1") (pin "19") (pinfunction "19_19") (pintype "passive"))
      (node (ref "J1") (pin "2") (pinfunction "2_2") (pintype "passive"))
      (node (ref "J1") (pin "32") (pinfunction "32_32") (pintype "passive"))
      (node (ref "J2") (pin "2") (pinfunction "2_2") (pintype "passive"))
      (node (ref "J2") (pin "38") (pinfunction "38_38") (pintype "passive"))
      (node (ref "J2") (pin "4") (pinfunction "4_4") (pintype "passive"))
      (node (ref "J2") (pin "44") (pinfunction "44_44") (pintype "passive"))
      (node (ref "U10") (pin "10") (pinfunction "B_10") (pintype "input"))
      (node (ref "U10") (pin "12") (pinfunction "C_12") (pintype "input"))
      (node (ref "U10") (pin "13") (pinfunction "D_13") (pintype "input"))
      (node (ref "U10") (pin "7") (pinfunction "GND_7") (pintype "power_in"))
      (node (ref "U10") (pin "9") (pinfunction "A_9") (pintype "input"))
      (node (ref "U3") (pin "T13") (pinfunction "OM3_T13") (pintype "input"))
      (node (ref "U3") (pin "U14") (pinfunction "OM2_U14") (pintype "input"))
      (node (ref "U4") (pin "12") (pinfunction "VSSQ_12") (pintype "power_in"))
      (node (ref "U4") (pin "28") (pinfunction "VSS_28") (pintype "power_in"))
      (node (ref "U4") (pin "41") (pinfunction "VSS_41") (pintype "power_in"))
      (node (ref "U4") (pin "46") (pinfunction "VSSQ_46") (pintype "power_in"))
      (node (ref "U4") (pin "52") (pinfunction "VSSQ_52") (pintype "power_in"))
      (node (ref "U4") (pin "54") (pinfunction "VSS_54") (pintype "power_in"))
      (node (ref "U4") (pin "6") (pinfunction "VSSQ_6") (pintype "power_in"))
      (node (ref "U5") (pin "10") (pinfunction "GND_10") (pintype "power_in"))
      (node (ref "U5") (pin "19") (pinfunction "~{OE}_19") (pintype "input"))
      (node (ref "U6") (pin "10") (pinfunction "GND_10") (pintype "power_in"))
      (node (ref "U7") (pin "10") (pinfunction "GND_10") (pintype "power_in"))
      (node (ref "U7") (pin "19") (pinfunction "~{OE}_19") (pintype "input"))
      (node (ref "U8") (pin "10") (pinfunction "GND_10") (pintype "power_in"))
      (node (ref "U9") (pin "13") (pinfunction "VSS_13") (pintype "passive"))
      (node (ref "U9") (pin "36") (pinfunction "VSS_36") (pintype "passive"))
      (node (ref "U9") (pin "6") (pinfunction "~{SE}_6") (pintype "passive"))
    )
    (net (code "144") (name "Net-(U3C-UPLLCAP)") (class "Default")
      (node (ref "C2") (pin "2") (pinfunction "2_2") (pintype "passive"))
      (node (ref "U3") (pin "L13") (pinfunction "UPLLCAP_L13") (pintype "passive"))
    )
    (net (code "145") (name "VCC") (class "Default")
      (node (ref "U10") (pin "14") (pinfunction "VCC_14") (pintype "power_in"))
    )
    (net (code "146") (name "VDD33") (class "Default")
      (node (ref "C10") (pin "1") (pinfunction "1_1") (pintype "passive"))
      (node (ref "C11") (pin "1") (pinfunction "1_1") (pintype "passive"))
      (node (ref "C12") (pin "1") (pinfunction "1_1") (pintype "passive"))
      (node (ref "C13") (pin "1") (pinfunction "1_1") (pintype "passive"))
      (node (ref "C14") (pin "1") (pinfunction "1_1") (pintype "passive"))
      (node (ref "C15") (pin "1") (pinfunction "1_1") (pintype "passive"))
      (node (ref "C16") (pin "1") (pinfunction "1_1") (pintype "passive"))
      (node (ref "C17") (pin "1") (pinfunction "1_1") (pintype "passive"))
      (node (ref "C18") (pin "1") (pinfunction "1_1") (pintype "passive"))
      (node (ref "C19") (pin "1") (pinfunction "1_1") (pintype "passive"))
      (node (ref "C20") (pin "1") (pinfunction "1_1") (pintype "passive"))
      (node (ref "C21") (pin "1") (pinfunction "1_1") (pintype "passive"))
      (node (ref "C22") (pin "1") (pinfunction "1_1") (pintype "passive"))
      (node (ref "C23") (pin "1") (pinfunction "1_1") (pintype "passive"))
      (node (ref "C7") (pin "1") (pinfunction "1_1") (pintype "passive"))
      (node (ref "C8") (pin "1") (pinfunction "1_1") (pintype "passive"))
      (node (ref "C9") (pin "1") (pinfunction "1_1") (pintype "passive"))
      (node (ref "J1") (pin "1") (pinfunction "1_1") (pintype "passive"))
      (node (ref "J2") (pin "3") (pinfunction "3_3") (pintype "passive"))
      (node (ref "R10") (pin "1") (pinfunction "1_1") (pintype "passive"))
      (node (ref "R11") (pin "1") (pinfunction "1_1") (pintype "passive"))
      (node (ref "R2") (pin "2") (pinfunction "2_2") (pintype "passive"))
      (node (ref "R3") (pin "2") (pinfunction "2_2") (pintype "passive"))
      (node (ref "U3") (pin "J11") (pinfunction "EXTCLK_J11") (pintype "input"))
      (node (ref "U3") (pin "J17") (pinfunction "nBATT_FLT_J17") (pintype "input"))
      (node (ref "U3") (pin "N12") (pinfunction "Vref_N12") (pintype "input"))
      (node (ref "U3") (pin "U13") (pinfunction "NCON_U13") (pintype "input"))
      (node (ref "U4") (pin "1") (pinfunction "VDD_1") (pintype "power_in"))
      (node (ref "U4") (pin "14") (pinfunction "VDD_14") (pintype "power_in"))
      (node (ref "U4") (pin "27") (pinfunction "VDD_27") (pintype "power_in"))
      (node (ref "U4") (pin "3") (pinfunction "VDDQ_3") (pintype "power_in"))
      (node (ref "U4") (pin "43") (pinfunction "VDDQ_43") (pintype "power_in"))
      (node (ref "U4") (pin "49") (pinfunction "VDDQ_49") (pintype "power_in"))
      (node (ref "U4") (pin "9") (pinfunction "VDDQ_9") (pintype "power_in"))
      (node (ref "U5") (pin "1") (pinfunction "T/~{R}_1") (pintype "input"))
      (node (ref "U5") (pin "20") (pinfunction "VCC_20") (pintype "power_in"))
      (node (ref "U6") (pin "20") (pinfunction "VCC_20") (pintype "power_in"))
      (node (ref "U7") (pin "1") (pinfunction "T/~{R}_1") (pintype "input"))
      (node (ref "U7") (pin "20") (pinfunction "VCC_20") (pintype "power_in"))
      (node (ref "U8") (pin "20") (pinfunction "VCC_20") (pintype "power_in"))
      (node (ref "U9") (pin "12") (pinfunction "VCC_12") (pintype "power_in"))
      (node (ref "U9") (pin "37") (pinfunction "VCC_37") (pintype "power_in"))
    )
    (net (code "147") (name "VDD50") (class "Default")
      (node (ref "J2") (pin "1") (pinfunction "1_1") (pintype "passive"))
    )
    (net (code "148") (name "VDDRTC") (class "Default")
      (node (ref "J2") (pin "43") (pinfunction "43_43") (pintype "passive"))
    )
    (net (code "149") (name "unconnected-(U3C-AIN4-PadR15)") (class "Default")
      (node (ref "U3") (pin "R15") (pinfunction "AIN4_R15") (pintype "input+no_connect"))
    )
    (net (code "150") (name "unconnected-(U3C-AIN6-PadR16)") (class "Default")
      (node (ref "U3") (pin "R16") (pinfunction "AIN6_R16") (pintype "input+no_connect"))
    )
    (net (code "151") (name "unconnected-(U3C-CLKOUT1{slash}GPH10-PadU12)") (class "Default")
      (node (ref "U3") (pin "U12") (pinfunction "CLKOUT1/GPH10_U12") (pintype "bidirectional+no_connect"))
    )
    (net (code "152") (name "unconnected-(U3C-PWREN-PadJ15)") (class "Default")
      (node (ref "U3") (pin "J15") (pinfunction "PWREN_J15") (pintype "output+no_connect"))
    )
    (net (code "153") (name "unconnected-(U3C-SCLK1-PadF14)") (class "Default")
      (node (ref "U3") (pin "F14") (pinfunction "SCLK1_F14") (pintype "output+no_connect"))
    )
    (net (code "154") (name "unconnected-(U3C-TOUT2{slash}GPB2-PadF4)") (class "Default")
      (node (ref "U3") (pin "F4") (pinfunction "TOUT2/GPB2_F4") (pintype "bidirectional+no_connect"))
    )
    (net (code "155") (name "unconnected-(U3C-TOUT3{slash}GPB3-PadG3)") (class "Default")
      (node (ref "U3") (pin "G3") (pinfunction "TOUT3/GPB3_G3") (pintype "bidirectional+no_connect"))
    )
    (net (code "156") (name "unconnected-(U3C-nBE2:nWBE2:DQM2-PadC15)") (class "Default")
      (node (ref "U3") (pin "C15") (pinfunction "nBE2:nWBE2:DQM2_C15") (pintype "tri_state+no_connect"))
    )
    (net (code "157") (name "unconnected-(U3C-nBE3:nWBE3:DQM3-PadA16)") (class "Default")
      (node (ref "U3") (pin "A16") (pinfunction "nBE3:nWBE3:DQM3_A16") (pintype "tri_state+no_connect"))
    )
    (net (code "158") (name "unconnected-(U3C-nRSTOUT{slash}GPA21-PadJ16)") (class "Default")
      (node (ref "U3") (pin "J16") (pinfunction "nRSTOUT/GPA21_J16") (pintype "output+no_connect"))
    )
    (net (code "159") (name "unconnected-(U4-NC{slash}RFU-Pad40)") (class "Default")
      (node (ref "U4") (pin "40") (pinfunction "NC/RFU_40") (pintype "passive"))
    )
    (net (code "160") (name "unconnected-(U10B-Y-Pad8)") (class "Default")
      (node (ref "U10") (pin "8") (pinfunction "Y_8") (pintype "output+no_connect"))
    )
  )
)
